# PowerSys.net
KiCad netlist of a schematic drawn in Altium Designer
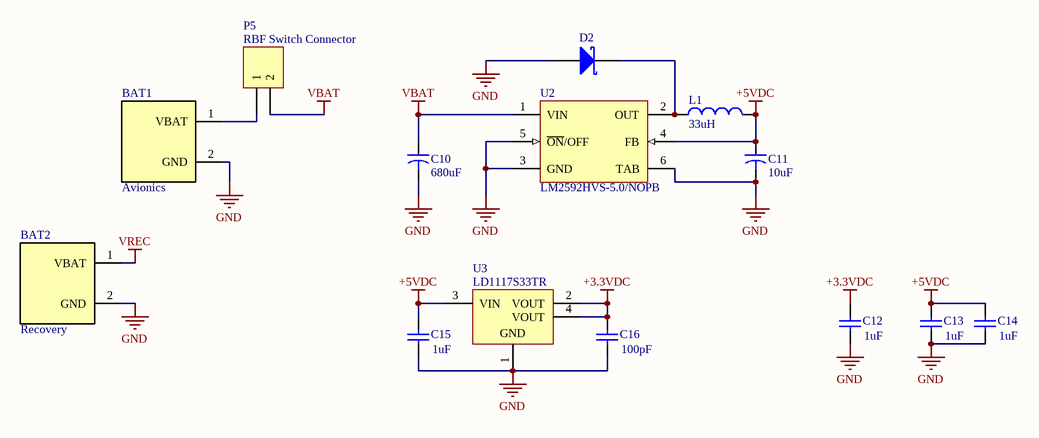
[diagram p0: PowerSys.SchDoc]

(export (version "E")
  (design (tool "Eeschema 10.0.6"))
  (components
    (comp (ref "BAT1") (value "Avionics") (footprint "XT30") (libsource (lib "CustomCompLib") (part "XT30")))
    (comp (ref "BAT2") (value "Recovery") (footprint "XT30") (libsource (lib "CustomCompLib") (part "XT30")))
    (comp (ref "C10")
      (value "680uF")
      (footprint "*CAPAE430X550N")
      (description "Capacitor")
      (fields (field (name "Comment") "Cap2") (field (name "PUBLISHER") "Altium Limited"))
      (libsource (lib "Miscellaneous Devices") (part "Cap2"))
    )
    (comp (ref "C11")
      (value "10uF")
      (footprint "*CAPAE430X550N")
      (description "Capacitor")
      (fields (field (name "Comment") "Cap2") (field (name "PUBLISHER") "Altium Limited"))
      (libsource (lib "Miscellaneous Devices") (part "Cap2"))
    )
    (comp (ref "C12")
      (value "1uF")
      (footprint "1608[0603]")
      (description "Capacitor (Semiconductor SIM Model)")
      (fields (field (name "Comment") "Cap Semi") (field (name "PUBLISHER") "Altium Limited"))
      (libsource (lib "Miscellaneous Devices") (part "Cap Semi"))
    )
    (comp (ref "C13")
      (value "1uF")
      (footprint "1608[0603]")
      (description "Capacitor (Semiconductor SIM Model)")
      (fields (field (name "Comment") "Cap Semi") (field (name "PUBLISHER") "Altium Limited"))
      (libsource (lib "Miscellaneous Devices") (part "Cap Semi"))
    )
    (comp (ref "C14")
      (value "1uF")
      (footprint "1608[0603]")
      (description "Capacitor (Semiconductor SIM Model)")
      (fields (field (name "Comment") "Cap Semi") (field (name "PUBLISHER") "Altium Limited"))
      (libsource (lib "Miscellaneous Devices") (part "Cap Semi"))
    )
    (comp (ref "C15")
      (value "1uF")
      (footprint "C1206")
      (description "Capacitor (Semiconductor SIM Model)")
      (fields (field (name "Comment") "Cap Semi") (field (name "PUBLISHER") "Altium Limited"))
      (libsource (lib "Miscellaneous Devices") (part "Cap Semi"))
    )
    (comp (ref "C16")
      (value "100pF")
      (footprint "C1206")
      (description "Capacitor (Semiconductor SIM Model)")
      (fields (field (name "Comment") "Cap Semi") (field (name "PUBLISHER") "Altium Limited"))
      (libsource (lib "Miscellaneous Devices") (part "Cap Semi"))
    )
    (comp (ref "D2")
      (value "D Schottky")
      (footprint "SMB")
      (description "Schottky Diode")
      (fields (field (name "PUBLISHER") "Altium Limited"))
      (libsource (lib "Miscellaneous Devices") (part "D Schottky"))
    )
    (comp (ref "L1")
      (value "33uH")
      (footprint "Inductor")
      (libsource (lib "CustomCompLib") (part "Inductor"))
    )
    (comp (ref "P5")
      (value "RBF Switch Connector")
      (footprint "HDR1X2")
      (description "Header, 2-Pin")
      (fields (field (name "PUBLISHER") "Altium Limited"))
      (libsource (lib "Miscellaneous Connectors") (part "Header 2"))
    )
    (comp (ref "U2")
      (value "LM2592HVS-5.0/NOPB")
      (footprint "TS5B_N")
      (description "SIMPLE SWITCHER® Power Converter 150 KHz 2A Step-Down Voltage Regulator, 5-pin TO-263, Pb-Free")
      (fields
        (field (name "MANUFACTURER") "National Semiconductor")
        (field (name "PUBLISHER") "Altium Limited")
      )
      (libsource (lib "NSC Switcher") (part "LM2592HVS-5.0/NOPB"))
    )
    (comp (ref "U3")
      (value "LD1117S33TR")
      (footprint "SOT-223_N")
      (description "Fixed Low Drop Positive Voltage Regulator, 3.3V, 4-Pin SOT-223, Tape and Reel")
      (libsource (lib "STMicroelectronics Power Management Linear Regulator") (part "LD1117S33TR"))
    )
  )
  (nets
    (net (code "1") (name "+3.3VDC") (class "Default")
      (node (ref "C12") (pin "2") (pinfunction "2_2") (pintype "passive"))
      (node (ref "C16") (pin "2") (pinfunction "2_2") (pintype "passive"))
      (node (ref "U3") (pin "2") (pinfunction "VOUT_2") (pintype "power_in"))
      (node (ref "U3") (pin "4") (pinfunction "VOUT_4") (pintype "power_in"))
    )
    (net (code "2") (name "+5VDC") (class "Default")
      (node (ref "C11") (pin "1") (pinfunction "1_1") (pintype "passive"))
      (node (ref "C13") (pin "2") (pinfunction "2_2") (pintype "passive"))
      (node (ref "C14") (pin "2") (pinfunction "2_2") (pintype "passive"))
      (node (ref "C15") (pin "2") (pinfunction "2_2") (pintype "passive"))
      (node (ref "L1") (pin "1") (pinfunction "1_1") (pintype "passive"))
      (node (ref "U2") (pin "4") (pinfunction "FB_4") (pintype "input"))
      (node (ref "U3") (pin "3") (pinfunction "VIN_3") (pintype "power_in"))
    )
    (net (code "3") (name "GND") (class "Default")
      (node (ref "BAT1") (pin "2") (pinfunction "GND_2") (pintype "passive"))
      (node (ref "BAT2") (pin "2") (pinfunction "GND_2") (pintype "passive"))
      (node (ref "C10") (pin "2") (pinfunction "2_2") (pintype "passive"))
      (node (ref "C11") (pin "2") (pinfunction "2_2") (pintype "passive"))
      (node (ref "C12") (pin "1") (pinfunction "1_1") (pintype "passive"))
      (node (ref "C13") (pin "1") (pinfunction "1_1") (pintype "passive"))
      (node (ref "C14") (pin "1") (pinfunction "1_1") (pintype "passive"))
      (node (ref "C15") (pin "1") (pinfunction "1_1") (pintype "passive"))
      (node (ref "C16") (pin "1") (pinfunction "1_1") (pintype "passive"))
      (node (ref "D2") (pin "1") (pinfunction "A_1") (pintype "passive"))
      (node (ref "U2") (pin "3") (pinfunction "GND_3") (pintype "power_in"))
      (node (ref "U2") (pin "5") (pinfunction "~{ON}/OFF_5") (pintype "input"))
      (node (ref "U2") (pin "6") (pinfunction "TAB_6") (pintype "power_in"))
      (node (ref "U3") (pin "1") (pinfunction "GND_1") (pintype "power_in"))
    )
    (net (code "4") (name "Net-(BAT1-VBAT)") (class "Default")
      (node (ref "BAT1") (pin "1") (pinfunction "VBAT_1") (pintype "passive"))
      (node (ref "P5") (pin "1") (pinfunction "1_1") (pintype "passive"))
    )
    (net (code "5") (name "Net-(D2-K)") (class "Default")
      (node (ref "D2") (pin "2") (pinfunction "K_2") (pintype "passive"))
      (node (ref "L1") (pin "2") (pinfunction "2_2") (pintype "passive"))
      (node (ref "U2") (pin "2") (pinfunction "OUT_2") (pintype "power_in"))
    )
    (net (code "6") (name "VBAT") (class "Default")
      (node (ref "C10") (pin "1") (pinfunction "1_1") (pintype "passive"))
      (node (ref "P5") (pin "2") (pinfunction "2_2") (pintype "passive"))
      (node (ref "U2") (pin "1") (pinfunction "VIN_1") (pintype "power_in"))
    )
    (net (code "7") (name "VREC") (class "Default")
      (node (ref "BAT2") (pin "1") (pinfunction "VBAT_1") (pintype "passive"))
    )
  )
)
